# RS232_RS485_IrDA.net
KiCad netlist of a schematic drawn in Altium Designer
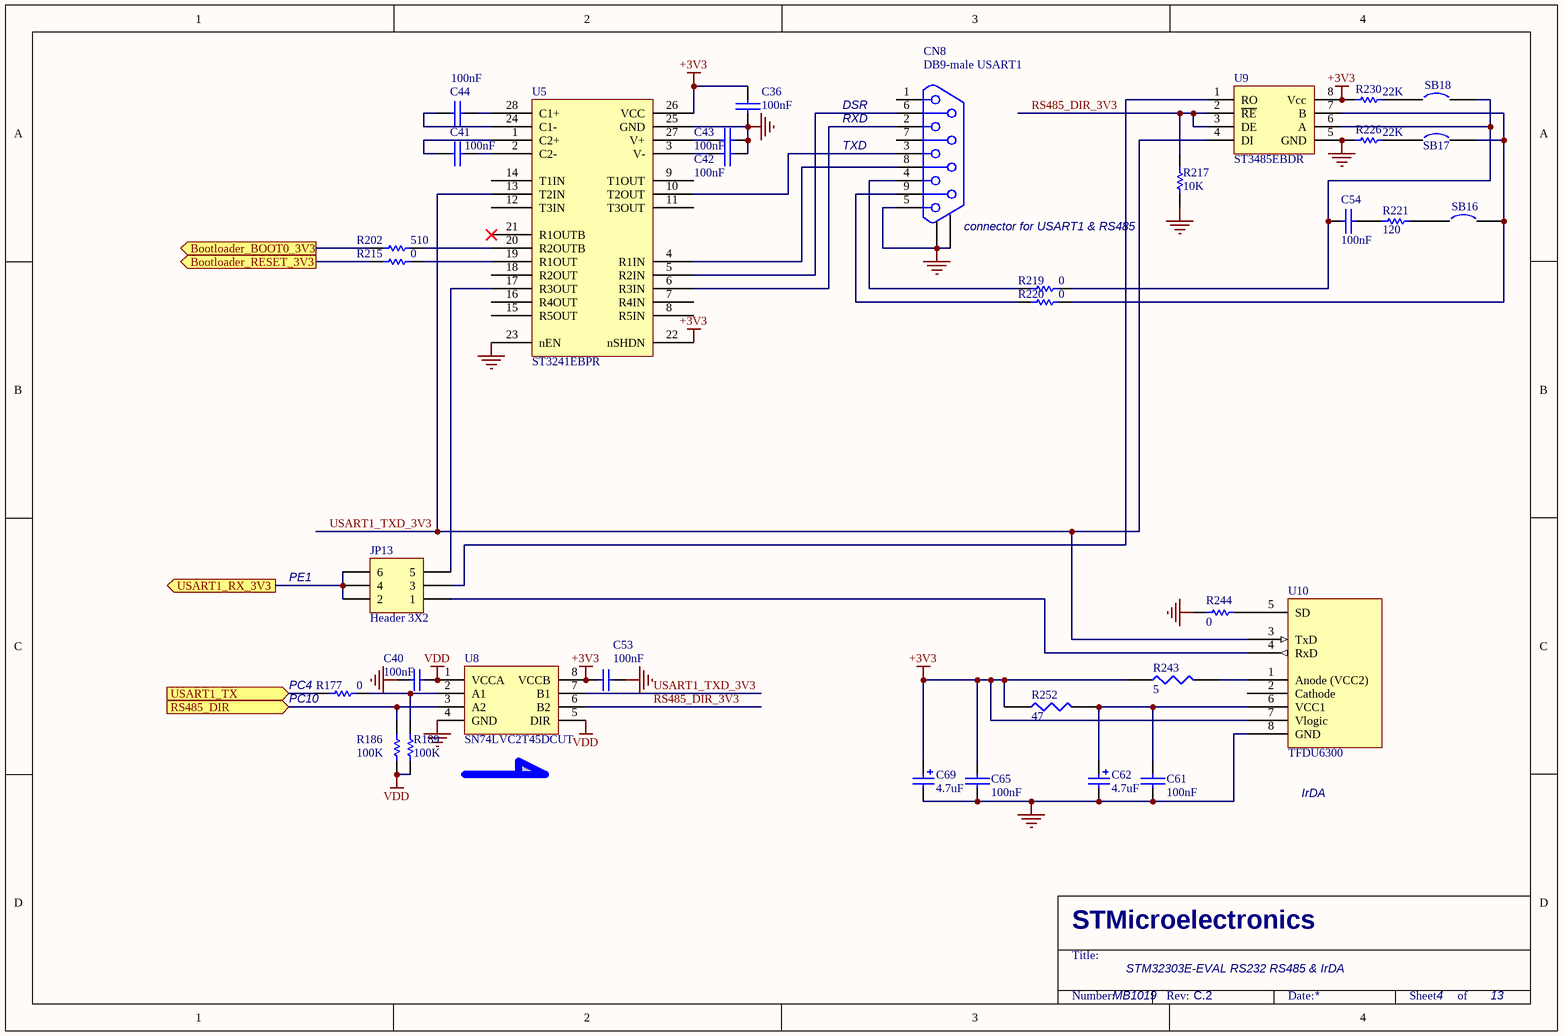
[diagram p0: RS232_RS485_IrDA.SchDoc]

(export (version "E")
  (design (tool "Eeschema 10.0.6"))
  (components
    (comp (ref "C36")
      (value "100nF")
      (footprint "0603C")
      (description "Capacitor")
      (libsource (lib "*") (part "CAP"))
    )
    (comp (ref "C40")
      (value "100nF")
      (footprint "0603C")
      (description "Capacitor")
      (fields (field (name "PUBLISHER") "Altium Limited"))
      (libsource (lib "Miscellaneous Devices") (part "CAP"))
    )
    (comp (ref "C41")
      (value "100nF")
      (footprint "0603C")
      (description "Capacitor")
      (libsource (lib "*") (part "CAP"))
    )
    (comp (ref "C42")
      (value "100nF")
      (footprint "0603C")
      (description "Capacitor")
      (libsource (lib "*") (part "CAP"))
    )
    (comp (ref "C43")
      (value "100nF")
      (footprint "0603C")
      (description "Capacitor")
      (libsource (lib "*") (part "CAP"))
    )
    (comp (ref "C44")
      (value "100nF")
      (footprint "0603C")
      (description "Capacitor")
      (libsource (lib "*") (part "CAP"))
    )
    (comp (ref "C53")
      (value "100nF")
      (footprint "0603C")
      (description "Capacitor")
      (fields (field (name "PUBLISHER") "Altium Limited"))
      (libsource (lib "Miscellaneous Devices") (part "CAP"))
    )
    (comp (ref "C54")
      (value "100nF")
      (footprint "0603C")
      (description "Capacitor")
      (libsource (lib "*") (part "CAP"))
    )
    (comp (ref "C61")
      (value "100nF")
      (footprint "0603C")
      (description "Capacitor")
      (libsource (lib "*") (part "CAP"))
    )
    (comp (ref "C62")
      (value "4.7uF")
      (footprint "TAN-A")
      (description "Polarized Capacitor (Radial)")
      (fields (field (name "PUBLISHER") "Altium Limited"))
      (libsource (lib "Miscellaneous Devices") (part "Cap Pol1"))
    )
    (comp (ref "C65")
      (value "100nF")
      (footprint "0603C")
      (description "Capacitor")
      (libsource (lib "*") (part "CAP"))
    )
    (comp (ref "C69")
      (value "4.7uF")
      (footprint "TAN-A")
      (description "Polarized Capacitor (Radial)")
      (fields (field (name "PUBLISHER") "Altium Limited"))
      (libsource (lib "Miscellaneous Devices") (part "Cap Pol1"))
    )
    (comp (ref "CN8") (value "DB9-male USART1") (footprint "DB9/M") (libsource (lib "*") (part "DB9")))
    (comp (ref "JP13")
      (value "Header 3X2")
      (footprint "2*3P")
      (description "Header, 3-Pin, Dual row")
      (fields (field (name "PUBLISHER") "Altium Limited"))
      (libsource (lib "Miscellaneous Connectors") (part "Header 3X2"))
    )
    (comp (ref "R177")
      (value "0")
      (footprint "0603R")
      (description "Resistor")
      (fields (field (name "PUBLISHER") "Altium Limited"))
      (libsource (lib "Miscellaneous Devices") (part "res1"))
    )
    (comp (ref "R186")
      (value "100K")
      (footprint "0603R")
      (description "Resistor")
      (fields (field (name "PUBLISHER") "Altium Limited"))
      (libsource (lib "Miscellaneous Devices") (part "Res1"))
    )
    (comp (ref "R189")
      (value "100K")
      (footprint "0603R")
      (description "Resistor")
      (fields (field (name "PUBLISHER") "Altium Limited"))
      (libsource (lib "Miscellaneous Devices") (part "Res1"))
    )
    (comp (ref "R202")
      (value "510")
      (footprint "0603R")
      (description "Resistor")
      (fields (field (name "PUBLISHER") "Altium Limited"))
      (libsource (lib "Miscellaneous Devices") (part "Res1"))
    )
    (comp (ref "R215")
      (value "0")
      (footprint "0603R")
      (description "Resistor")
      (fields (field (name "PUBLISHER") "Altium Limited"))
      (libsource (lib "Miscellaneous Devices") (part "Res1"))
    )
    (comp (ref "R217")
      (value "10K")
      (footprint "0603R")
      (description "Resistor")
      (fields (field (name "PUBLISHER") "Altium Limited"))
      (libsource (lib "Miscellaneous Devices") (part "Res1"))
    )
    (comp (ref "R219")
      (value "0")
      (footprint "0603R")
      (description "Resistor")
      (fields (field (name "PUBLISHER") "Altium Limited"))
      (libsource (lib "Miscellaneous Devices") (part "Res1"))
    )
    (comp (ref "R220")
      (value "0")
      (footprint "0603R")
      (description "Resistor")
      (fields (field (name "PUBLISHER") "Altium Limited"))
      (libsource (lib "Miscellaneous Devices") (part "Res1"))
    )
    (comp (ref "R221")
      (value "120")
      (footprint "0603R")
      (description "Resistor")
      (fields (field (name "PUBLISHER") "Altium Limited"))
      (libsource (lib "Miscellaneous Devices") (part "Res1"))
    )
    (comp (ref "R226")
      (value "22K")
      (footprint "0603R")
      (description "Resistor")
      (fields (field (name "PUBLISHER") "Altium Limited"))
      (libsource (lib "Miscellaneous Devices") (part "Res1"))
    )
    (comp (ref "R230")
      (value "22K")
      (footprint "0603R")
      (description "Resistor")
      (fields (field (name "PUBLISHER") "Altium Limited"))
      (libsource (lib "Miscellaneous Devices") (part "Res1"))
    )
    (comp (ref "R243") (value "5") (footprint "0603R") (libsource (lib "*") (part "RES1")))
    (comp (ref "R244")
      (value "0")
      (footprint "0603R")
      (description "Resistor")
      (fields (field (name "PUBLISHER") "Altium Limited"))
      (libsource (lib "Miscellaneous Devices") (part "Res1"))
    )
    (comp (ref "R252") (value "47") (footprint "0603R") (libsource (lib "*") (part "RES1")))
    (comp (ref "SB16")
      (value "~")
      (footprint "JP2_SMD")
      (description "Circuit Breaker")
      (fields (field (name "PUBLISHER") "Altium Limited"))
      (libsource (lib "Miscellaneous Devices") (part "Circuit Breaker"))
    )
    (comp (ref "SB17")
      (value "~")
      (footprint "JP2_SMD")
      (description "Circuit Breaker")
      (fields (field (name "PUBLISHER") "Altium Limited"))
      (libsource (lib "Miscellaneous Devices") (part "Circuit Breaker"))
    )
    (comp (ref "SB18")
      (value "~")
      (footprint "JP2_SMD")
      (description "Circuit Breaker")
      (fields (field (name "PUBLISHER") "Altium Limited"))
      (libsource (lib "Miscellaneous Devices") (part "Circuit Breaker"))
    )
    (comp (ref "U5") (value "ST3241EBPR") (footprint "SSOP28") (libsource (lib "*") (part "ST3241")))
    (comp (ref "U8")
      (value "SN74LVC2T45DCUT")
      (footprint "VSSOP8")
      (libsource (lib "MB818") (part "SN74LVC2T45DCUT"))
    )
    (comp (ref "U9") (value "ST3485EBDR") (footprint "SO8") (libsource (lib "MB901") (part "ST485ABDR")))
    (comp (ref "U10")
      (value "TFDU6300")
      (footprint "IR_VISHAY3")
      (description "TFDU4300")
      (libsource (lib "*") (part "TFDU4300"))
    )
  )
  (nets
    (net (code "1") (name "+3V3") (class "Default")
      (node (ref "C36") (pin "2") (pinfunction "2_2") (pintype "passive"))
      (node (ref "C53") (pin "2") (pinfunction "2_2") (pintype "passive"))
      (node (ref "C65") (pin "1") (pinfunction "1_1") (pintype "passive"))
      (node (ref "C69") (pin "1") (pinfunction "1_1") (pintype "passive"))
      (node (ref "R230") (pin "2") (pinfunction "2_2") (pintype "passive"))
      (node (ref "R243") (pin "1") (pinfunction "1_1") (pintype "passive"))
      (node (ref "R252") (pin "1") (pinfunction "1_1") (pintype "passive"))
      (node (ref "U10") (pin "7") (pinfunction "Vlogic_7") (pintype "passive"))
      (node (ref "U5") (pin "22") (pinfunction "nSHDN_22") (pintype "passive"))
      (node (ref "U5") (pin "26") (pinfunction "VCC_26") (pintype "passive"))
      (node (ref "U8") (pin "8") (pinfunction "VCCB_8") (pintype "passive"))
      (node (ref "U9") (pin "8") (pinfunction "Vcc_8") (pintype "passive"))
    )
    (net (code "2") (name "/Bootloader_BOOT0_3V3") (class "Default")
      (node (ref "R202") (pin "1") (pinfunction "1_1") (pintype "passive"))
    )
    (net (code "3") (name "/Bootloader_RESET_3V3") (class "Default")
      (node (ref "R215") (pin "1") (pinfunction "1_1") (pintype "passive"))
    )
    (net (code "4") (name "/RS485_DIR") (class "Default")
      (node (ref "R186") (pin "1") (pinfunction "1_1") (pintype "passive"))
      (node (ref "U8") (pin "3") (pinfunction "A2_3") (pintype "passive"))
    )
    (net (code "5") (name "/RS485_DIR_3V3") (class "Default")
      (node (ref "R217") (pin "2") (pinfunction "2_2") (pintype "passive"))
      (node (ref "U8") (pin "6") (pinfunction "B2_6") (pintype "passive"))
      (node (ref "U9") (pin "2") (pinfunction "~{RE}_2") (pintype "passive"))
      (node (ref "U9") (pin "3") (pinfunction "DE_3") (pintype "passive"))
    )
    (net (code "6") (name "/USART1_RX_3V3") (class "Default")
      (node (ref "JP13") (pin "2") (pinfunction "2_2") (pintype "passive"))
      (node (ref "JP13") (pin "4") (pinfunction "4_4") (pintype "passive"))
      (node (ref "JP13") (pin "6") (pinfunction "6_6") (pintype "passive"))
    )
    (net (code "7") (name "/USART1_TX") (class "Default")
      (node (ref "R177") (pin "2") (pinfunction "2_2") (pintype "passive"))
    )
    (net (code "8") (name "/USART1_TXD_3V3") (class "Default")
      (node (ref "U10") (pin "3") (pinfunction "TxD_3") (pintype "input"))
      (node (ref "U5") (pin "13") (pinfunction "T2IN_13") (pintype "passive"))
      (node (ref "U8") (pin "7") (pinfunction "B1_7") (pintype "passive"))
      (node (ref "U9") (pin "4") (pinfunction "DI_4") (pintype "passive"))
    )
    (net (code "9") (name "GND") (class "Default")
      (node (ref "C36") (pin "1") (pinfunction "1_1") (pintype "passive"))
      (node (ref "C40") (pin "1") (pinfunction "1_1") (pintype "passive"))
      (node (ref "C42") (pin "2") (pinfunction "2_2") (pintype "passive"))
      (node (ref "C43") (pin "2") (pinfunction "2_2") (pintype "passive"))
      (node (ref "C53") (pin "1") (pinfunction "1_1") (pintype "passive"))
      (node (ref "C61") (pin "2") (pinfunction "2_2") (pintype "passive"))
      (node (ref "C62") (pin "2") (pinfunction "2_2") (pintype "passive"))
      (node (ref "C65") (pin "2") (pinfunction "2_2") (pintype "passive"))
      (node (ref "C69") (pin "2") (pinfunction "2_2") (pintype "passive"))
      (node (ref "CN8") (pin "0") (pinfunction "10_0") (pintype "passive"))
      (node (ref "CN8") (pin "5") (pinfunction "5_5") (pintype "passive"))
      (node (ref "R217") (pin "1") (pinfunction "1_1") (pintype "passive"))
      (node (ref "R226") (pin "2") (pinfunction "2_2") (pintype "passive"))
      (node (ref "R244") (pin "2") (pinfunction "2_2") (pintype "passive"))
      (node (ref "U10") (pin "8") (pinfunction "GND_8") (pintype "passive"))
      (node (ref "U5") (pin "23") (pinfunction "nEN_23") (pintype "passive"))
      (node (ref "U5") (pin "25") (pinfunction "GND_25") (pintype "passive"))
      (node (ref "U8") (pin "4") (pinfunction "GND_4") (pintype "passive"))
      (node (ref "U9") (pin "5") (pinfunction "GND_5") (pintype "passive"))
    )
    (net (code "10") (name "Net-(C54-Pad1)") (class "Default")
      (node (ref "C54") (pin "1") (pinfunction "1_1") (pintype "passive"))
      (node (ref "R221") (pin "1") (pinfunction "1_1") (pintype "passive"))
    )
    (net (code "11") (name "Net-(CN8-Pad4)") (class "Default")
      (node (ref "CN8") (pin "4") (pinfunction "4_4") (pintype "passive"))
      (node (ref "R219") (pin "2") (pinfunction "2_2") (pintype "passive"))
    )
    (net (code "12") (name "Net-(CN8-Pad9)") (class "Default")
      (node (ref "CN8") (pin "9") (pinfunction "9_9") (pintype "passive"))
      (node (ref "R220") (pin "2") (pinfunction "2_2") (pintype "passive"))
    )
    (net (code "13") (name "Net-(R221-Pad2)") (class "Default")
      (node (ref "R221") (pin "2") (pinfunction "2_2") (pintype "passive"))
      (node (ref "SB16") (pin "1") (pinfunction "1_1") (pintype "passive"))
    )
    (net (code "14") (name "Net-(R226-Pad1)") (class "Default")
      (node (ref "R226") (pin "1") (pinfunction "1_1") (pintype "passive"))
      (node (ref "SB17") (pin "1") (pinfunction "1_1") (pintype "passive"))
    )
    (net (code "15") (name "Net-(R230-Pad1)") (class "Default")
      (node (ref "R230") (pin "1") (pinfunction "1_1") (pintype "passive"))
      (node (ref "SB18") (pin "1") (pinfunction "1_1") (pintype "passive"))
    )
    (net (code "16") (name "Net-(U5-C1+)") (class "Default")
      (node (ref "C44") (pin "2") (pinfunction "2_2") (pintype "passive"))
      (node (ref "U5") (pin "28") (pinfunction "C1+_28") (pintype "passive"))
    )
    (net (code "17") (name "Net-(U5-C1-)") (class "Default")
      (node (ref "C44") (pin "1") (pinfunction "1_1") (pintype "passive"))
      (node (ref "U5") (pin "24") (pinfunction "C1-_24") (pintype "passive"))
    )
    (net (code "18") (name "Net-(U5-C2+)") (class "Default")
      (node (ref "C41") (pin "1") (pinfunction "1_1") (pintype "passive"))
      (node (ref "U5") (pin "1") (pinfunction "C2+_1") (pintype "passive"))
    )
    (net (code "19") (name "Net-(U5-C2-)") (class "Default")
      (node (ref "C41") (pin "2") (pinfunction "2_2") (pintype "passive"))
      (node (ref "U5") (pin "2") (pinfunction "C2-_2") (pintype "passive"))
    )
    (net (code "20") (name "Net-(U5-R1IN)") (class "Default")
      (node (ref "CN8") (pin "8") (pinfunction "8_8") (pintype "passive"))
      (node (ref "U5") (pin "4") (pinfunction "R1IN_4") (pintype "passive"))
    )
    (net (code "21") (name "Net-(U5-R1OUT)") (class "Default")
      (node (ref "R215") (pin "2") (pinfunction "2_2") (pintype "passive"))
      (node (ref "U5") (pin "19") (pinfunction "R1OUT_19") (pintype "passive"))
    )
    (net (code "22") (name "Net-(U5-R2IN)") (class "Default")
      (node (ref "CN8") (pin "6") (pinfunction "6_6") (pintype "passive"))
      (node (ref "U5") (pin "5") (pinfunction "R2IN_5") (pintype "passive"))
    )
    (net (code "23") (name "Net-(U5-R2OUTB)") (class "Default")
      (node (ref "R202") (pin "2") (pinfunction "2_2") (pintype "passive"))
      (node (ref "U5") (pin "20") (pinfunction "R2OUTB_20") (pintype "passive"))
    )
    (net (code "24") (name "Net-(U5-R3IN)") (class "Default")
      (node (ref "CN8") (pin "2") (pinfunction "2_2") (pintype "passive"))
      (node (ref "U5") (pin "6") (pinfunction "R3IN_6") (pintype "passive"))
    )
    (net (code "25") (name "Net-(U5-R3OUT)") (class "Default")
      (node (ref "JP13") (pin "5") (pinfunction "5_5") (pintype "passive"))
      (node (ref "U5") (pin "17") (pinfunction "R3OUT_17") (pintype "passive"))
    )
    (net (code "26") (name "Net-(U5-T2OUT)") (class "Default")
      (node (ref "CN8") (pin "3") (pinfunction "3_3") (pintype "passive"))
      (node (ref "U5") (pin "10") (pinfunction "T2OUT_10") (pintype "passive"))
    )
    (net (code "27") (name "Net-(U5-V+)") (class "Default")
      (node (ref "C43") (pin "1") (pinfunction "1_1") (pintype "passive"))
      (node (ref "U5") (pin "27") (pinfunction "V+_27") (pintype "passive"))
    )
    (net (code "28") (name "Net-(U5-V-)") (class "Default")
      (node (ref "C42") (pin "1") (pinfunction "1_1") (pintype "passive"))
      (node (ref "U5") (pin "3") (pinfunction "V-_3") (pintype "passive"))
    )
    (net (code "29") (name "Net-(U8-A1)") (class "Default")
      (node (ref "R177") (pin "1") (pinfunction "1_1") (pintype "passive"))
      (node (ref "R189") (pin "1") (pinfunction "1_1") (pintype "passive"))
      (node (ref "U8") (pin "2") (pinfunction "A1_2") (pintype "passive"))
    )
    (net (code "30") (name "Net-(U9-A)") (class "Default")
      (node (ref "C54") (pin "2") (pinfunction "2_2") (pintype "passive"))
      (node (ref "R219") (pin "1") (pinfunction "1_1") (pintype "passive"))
      (node (ref "SB18") (pin "2") (pinfunction "2_2") (pintype "passive"))
      (node (ref "U9") (pin "6") (pinfunction "A_6") (pintype "passive"))
    )
    (net (code "31") (name "Net-(U9-B)") (class "Default")
      (node (ref "R220") (pin "1") (pinfunction "1_1") (pintype "passive"))
      (node (ref "SB16") (pin "2") (pinfunction "2_2") (pintype "passive"))
      (node (ref "SB17") (pin "2") (pinfunction "2_2") (pintype "passive"))
      (node (ref "U9") (pin "7") (pinfunction "B_7") (pintype "passive"))
    )
    (net (code "32") (name "Net-(U9-RO)") (class "Default")
      (node (ref "JP13") (pin "3") (pinfunction "3_3") (pintype "passive"))
      (node (ref "U9") (pin "1") (pinfunction "RO_1") (pintype "passive"))
    )
    (net (code "33") (name "Net-(U10-Anode_(VCC2))") (class "Default")
      (node (ref "R243") (pin "2") (pinfunction "2_2") (pintype "passive"))
      (node (ref "U10") (pin "1") (pinfunction "Anode_(VCC2)_1") (pintype "passive"))
    )
    (net (code "34") (name "Net-(U10-RxD)") (class "Default")
      (node (ref "JP13") (pin "1") (pinfunction "1_1") (pintype "passive"))
      (node (ref "U10") (pin "4") (pinfunction "RxD_4") (pintype "output"))
    )
    (net (code "35") (name "Net-(U10-SD)") (class "Default")
      (node (ref "R244") (pin "1") (pinfunction "1_1") (pintype "passive"))
      (node (ref "U10") (pin "5") (pinfunction "SD_5") (pintype "passive"))
    )
    (net (code "36") (name "Net-(U10-VCC1)") (class "Default")
      (node (ref "C61") (pin "1") (pinfunction "1_1") (pintype "passive"))
      (node (ref "C62") (pin "1") (pinfunction "1_1") (pintype "passive"))
      (node (ref "R252") (pin "2") (pinfunction "2_2") (pintype "passive"))
      (node (ref "U10") (pin "6") (pinfunction "VCC1_6") (pintype "passive"))
    )
    (net (code "37") (name "VDD") (class "Default")
      (node (ref "C40") (pin "2") (pinfunction "2_2") (pintype "passive"))
      (node (ref "R186") (pin "2") (pinfunction "2_2") (pintype "passive"))
      (node (ref "R189") (pin "2") (pinfunction "2_2") (pintype "passive"))
      (node (ref "U8") (pin "1") (pinfunction "VCCA_1") (pintype "passive"))
      (node (ref "U8") (pin "5") (pinfunction "DIR_5") (pintype "passive"))
    )
    (net (code "38") (name "unconnected-(CN8-Pad1)") (class "Default")
      (node (ref "CN8") (pin "1") (pinfunction "1_1") (pintype "passive"))
    )
    (net (code "39") (name "unconnected-(CN8-Pad7)") (class "Default")
      (node (ref "CN8") (pin "7") (pinfunction "7_7") (pintype "passive"))
    )
    (net (code "40") (name "unconnected-(U5-R1OUTB-Pad21)") (class "Default")
      (node (ref "U5") (pin "21") (pinfunction "R1OUTB_21") (pintype "passive+no_connect"))
    )
    (net (code "41") (name "unconnected-(U5-R2OUT-Pad18)") (class "Default")
      (node (ref "U5") (pin "18") (pinfunction "R2OUT_18") (pintype "passive"))
    )
    (net (code "42") (name "unconnected-(U5-R4IN-Pad7)") (class "Default")
      (node (ref "U5") (pin "7") (pinfunction "R4IN_7") (pintype "passive"))
    )
    (net (code "43") (name "unconnected-(U5-R4OUT-Pad16)") (class "Default")
      (node (ref "U5") (pin "16") (pinfunction "R4OUT_16") (pintype "passive"))
    )
    (net (code "44") (name "unconnected-(U5-R5IN-Pad8)") (class "Default")
      (node (ref "U5") (pin "8") (pinfunction "R5IN_8") (pintype "passive"))
    )
    (net (code "45") (name "unconnected-(U5-R5OUT-Pad15)") (class "Default")
      (node (ref "U5") (pin "15") (pinfunction "R5OUT_15") (pintype "passive"))
    )
    (net (code "46") (name "unconnected-(U5-T1IN-Pad14)") (class "Default")
      (node (ref "U5") (pin "14") (pinfunction "T1IN_14") (pintype "passive"))
    )
    (net (code "47") (name "unconnected-(U5-T1OUT-Pad9)") (class "Default")
      (node (ref "U5") (pin "9") (pinfunction "T1OUT_9") (pintype "passive"))
    )
    (net (code "48") (name "unconnected-(U5-T3IN-Pad12)") (class "Default")
      (node (ref "U5") (pin "12") (pinfunction "T3IN_12") (pintype "passive"))
    )
    (net (code "49") (name "unconnected-(U5-T3OUT-Pad11)") (class "Default")
      (node (ref "U5") (pin "11") (pinfunction "T3OUT_11") (pintype "passive"))
    )
    (net (code "50") (name "unconnected-(U10-Cathode-Pad2)") (class "Default")
      (node (ref "U10") (pin "2") (pinfunction "Cathode_2") (pintype "passive"))
    )
  )
)
